# PowerDist.net
KiCad netlist of a schematic drawn in EAGLE
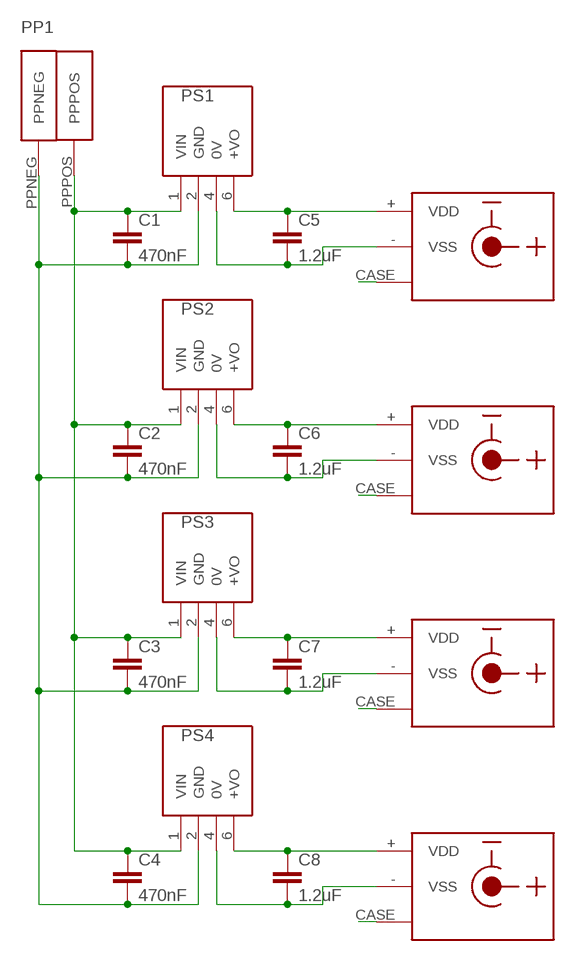
[diagram p0: schematic, sheet 1]

(export (version "E")
  (design (tool "Eeschema 10.0.6"))
  (components
    (comp (ref "C1")
      (value "470nF")
      (footprint "eagle-import:C5B2.5")
      (libsource (lib "eagle-import") (part "C5/2.5"))
    )
    (comp (ref "C2")
      (value "470nF")
      (footprint "eagle-import:C5B2.5")
      (libsource (lib "eagle-import") (part "C5/2.5"))
    )
    (comp (ref "C3")
      (value "470nF")
      (footprint "eagle-import:C5B2.5")
      (libsource (lib "eagle-import") (part "C5/2.5"))
    )
    (comp (ref "C4")
      (value "470nF")
      (footprint "eagle-import:C5B2.5")
      (libsource (lib "eagle-import") (part "C5/2.5"))
    )
    (comp (ref "C5")
      (value "1.2uF")
      (footprint "eagle-import:C2.5-3")
      (libsource (lib "eagle-import") (part "C2,5-3"))
    )
    (comp (ref "C6")
      (value "1.2uF")
      (footprint "eagle-import:C2.5-3")
      (libsource (lib "eagle-import") (part "C2,5-3"))
    )
    (comp (ref "C7")
      (value "1.2uF")
      (footprint "eagle-import:C2.5-3")
      (libsource (lib "eagle-import") (part "C2,5-3"))
    )
    (comp (ref "C8")
      (value "1.2uF")
      (footprint "eagle-import:C2.5-3")
      (libsource (lib "eagle-import") (part "C2,5-3"))
    )
    (comp (ref "PP1")
      (value "POWER_POLES_WINGS")
      (footprint "eagle-import:POWERPOLE_PAIR_WINGS")
      (libsource (lib "eagle-import") (part "POWER_POLES_WINGS"))
    )
    (comp (ref "PS1")
      (value "PRMCE1-S12-S15-S")
      (footprint "eagle-import:PRMCE1S12S15S")
      (fields (field (name "MOUSER_PART_NUMBER") "490-PRMCE1-S12-S15-S"))
      (libsource (lib "eagle-import") (part "PRMCE1-S12-S15-S"))
    )
    (comp (ref "PS2")
      (value "PRMCE1-S12-S15-S")
      (footprint "eagle-import:PRMCE1S12S15S")
      (fields (field (name "MOUSER_PART_NUMBER") "490-PRMCE1-S12-S15-S"))
      (libsource (lib "eagle-import") (part "PRMCE1-S12-S15-S"))
    )
    (comp (ref "PS3")
      (value "PRMCE1-S12-S15-S")
      (footprint "eagle-import:PRMCE1S12S15S")
      (fields (field (name "MOUSER_PART_NUMBER") "490-PRMCE1-S12-S15-S"))
      (libsource (lib "eagle-import") (part "PRMCE1-S12-S15-S"))
    )
    (comp (ref "PS4")
      (value "PRMCE1-S12-S15-S")
      (footprint "eagle-import:PRMCE1S12S15S")
      (fields (field (name "MOUSER_PART_NUMBER") "490-PRMCE1-S12-S15-S"))
      (libsource (lib "eagle-import") (part "PRMCE1-S12-S15-S"))
    )
    (comp (ref "U$1")
      (value "CUI_PJ-102A")
      (footprint "eagle-import:CUI_DCJACK_PCB")
      (libsource (lib "eagle-import") (part "CUI_PJ-102A"))
    )
    (comp (ref "U$2")
      (value "CUI_PJ-102A")
      (footprint "eagle-import:CUI_DCJACK_PCB")
      (libsource (lib "eagle-import") (part "CUI_PJ-102A"))
    )
    (comp (ref "U$3")
      (value "CUI_PJ-102A")
      (footprint "eagle-import:CUI_DCJACK_PCB")
      (libsource (lib "eagle-import") (part "CUI_PJ-102A"))
    )
    (comp (ref "U$4")
      (value "CUI_PJ-102A")
      (footprint "eagle-import:CUI_DCJACK_PCB")
      (libsource (lib "eagle-import") (part "CUI_PJ-102A"))
    )
  )
  (nets
    (net (code "1") (name "Net-(PS1-+VO)") (class "Default")
      (node (ref "C5") (pin "1") (pinfunction "1_1") (pintype "passive"))
      (node (ref "PS1") (pin "6") (pinfunction "+VO_6") (pintype "bidirectional"))
      (node (ref "U$1") (pin "+") (pinfunction "VDD_+") (pintype "power_in"))
    )
    (net (code "2") (name "Net-(PS1-0V)") (class "Default")
      (node (ref "C5") (pin "2") (pinfunction "2_2") (pintype "passive"))
      (node (ref "PS1") (pin "4") (pinfunction "0V_4") (pintype "bidirectional"))
      (node (ref "U$1") (pin "-") (pinfunction "VSS_-") (pintype "power_in"))
    )
    (net (code "3") (name "Net-(PS1-GND)") (class "Default")
      (node (ref "C1") (pin "2") (pinfunction "2_2") (pintype "passive"))
      (node (ref "C2") (pin "2") (pinfunction "2_2") (pintype "passive"))
      (node (ref "C3") (pin "2") (pinfunction "2_2") (pintype "passive"))
      (node (ref "C4") (pin "2") (pinfunction "2_2") (pintype "passive"))
      (node (ref "PP1") (pin "PPNEG") (pinfunction "PPNEG_PPNEG") (pintype "input"))
      (node (ref "PS1") (pin "2") (pinfunction "GND_2") (pintype "bidirectional"))
      (node (ref "PS2") (pin "2") (pinfunction "GND_2") (pintype "bidirectional"))
      (node (ref "PS3") (pin "2") (pinfunction "GND_2") (pintype "bidirectional"))
      (node (ref "PS4") (pin "2") (pinfunction "GND_2") (pintype "bidirectional"))
    )
    (net (code "4") (name "Net-(PS1-VIN)") (class "Default")
      (node (ref "C1") (pin "1") (pinfunction "1_1") (pintype "passive"))
      (node (ref "C2") (pin "1") (pinfunction "1_1") (pintype "passive"))
      (node (ref "C3") (pin "1") (pinfunction "1_1") (pintype "passive"))
      (node (ref "C4") (pin "1") (pinfunction "1_1") (pintype "passive"))
      (node (ref "PP1") (pin "PPPOS") (pinfunction "PPPOS_PPPOS") (pintype "input"))
      (node (ref "PS1") (pin "1") (pinfunction "VIN_1") (pintype "bidirectional"))
      (node (ref "PS2") (pin "1") (pinfunction "VIN_1") (pintype "bidirectional"))
      (node (ref "PS3") (pin "1") (pinfunction "VIN_1") (pintype "bidirectional"))
      (node (ref "PS4") (pin "1") (pinfunction "VIN_1") (pintype "bidirectional"))
    )
    (net (code "5") (name "Net-(PS2-+VO)") (class "Default")
      (node (ref "C6") (pin "1") (pinfunction "1_1") (pintype "passive"))
      (node (ref "PS2") (pin "6") (pinfunction "+VO_6") (pintype "bidirectional"))
      (node (ref "U$2") (pin "+") (pinfunction "VDD_+") (pintype "power_in"))
    )
    (net (code "6") (name "Net-(PS2-0V)") (class "Default")
      (node (ref "C6") (pin "2") (pinfunction "2_2") (pintype "passive"))
      (node (ref "PS2") (pin "4") (pinfunction "0V_4") (pintype "bidirectional"))
      (node (ref "U$2") (pin "-") (pinfunction "VSS_-") (pintype "power_in"))
    )
    (net (code "7") (name "Net-(PS3-+VO)") (class "Default")
      (node (ref "C7") (pin "1") (pinfunction "1_1") (pintype "passive"))
      (node (ref "PS3") (pin "6") (pinfunction "+VO_6") (pintype "bidirectional"))
      (node (ref "U$3") (pin "+") (pinfunction "VDD_+") (pintype "power_in"))
    )
    (net (code "8") (name "Net-(PS3-0V)") (class "Default")
      (node (ref "C7") (pin "2") (pinfunction "2_2") (pintype "passive"))
      (node (ref "PS3") (pin "4") (pinfunction "0V_4") (pintype "bidirectional"))
      (node (ref "U$3") (pin "-") (pinfunction "VSS_-") (pintype "power_in"))
    )
    (net (code "9") (name "Net-(PS4-+VO)") (class "Default")
      (node (ref "C8") (pin "1") (pinfunction "1_1") (pintype "passive"))
      (node (ref "PS4") (pin "6") (pinfunction "+VO_6") (pintype "bidirectional"))
      (node (ref "U$4") (pin "+") (pinfunction "VDD_+") (pintype "power_in"))
    )
    (net (code "10") (name "Net-(PS4-0V)") (class "Default")
      (node (ref "C8") (pin "2") (pinfunction "2_2") (pintype "passive"))
      (node (ref "PS4") (pin "4") (pinfunction "0V_4") (pintype "bidirectional"))
      (node (ref "U$4") (pin "-") (pinfunction "VSS_-") (pintype "power_in"))
    )
    (net (code "11") (name "unconnected-(U$1-PadCASE)") (class "Default")
      (node (ref "U$1") (pin "CASE") (pintype "power_in"))
    )
    (net (code "12") (name "unconnected-(U$2-PadCASE)") (class "Default")
      (node (ref "U$2") (pin "CASE") (pintype "power_in"))
    )
    (net (code "13") (name "unconnected-(U$3-PadCASE)") (class "Default")
      (node (ref "U$3") (pin "CASE") (pintype "power_in"))
    )
    (net (code "14") (name "unconnected-(U$4-PadCASE)") (class "Default")
      (node (ref "U$4") (pin "CASE") (pintype "power_in"))
    )
  )
)
